# SENSOR_TESTER_EAGLE_SCHEMATIC.net
KiCad netlist of a schematic drawn in EAGLE
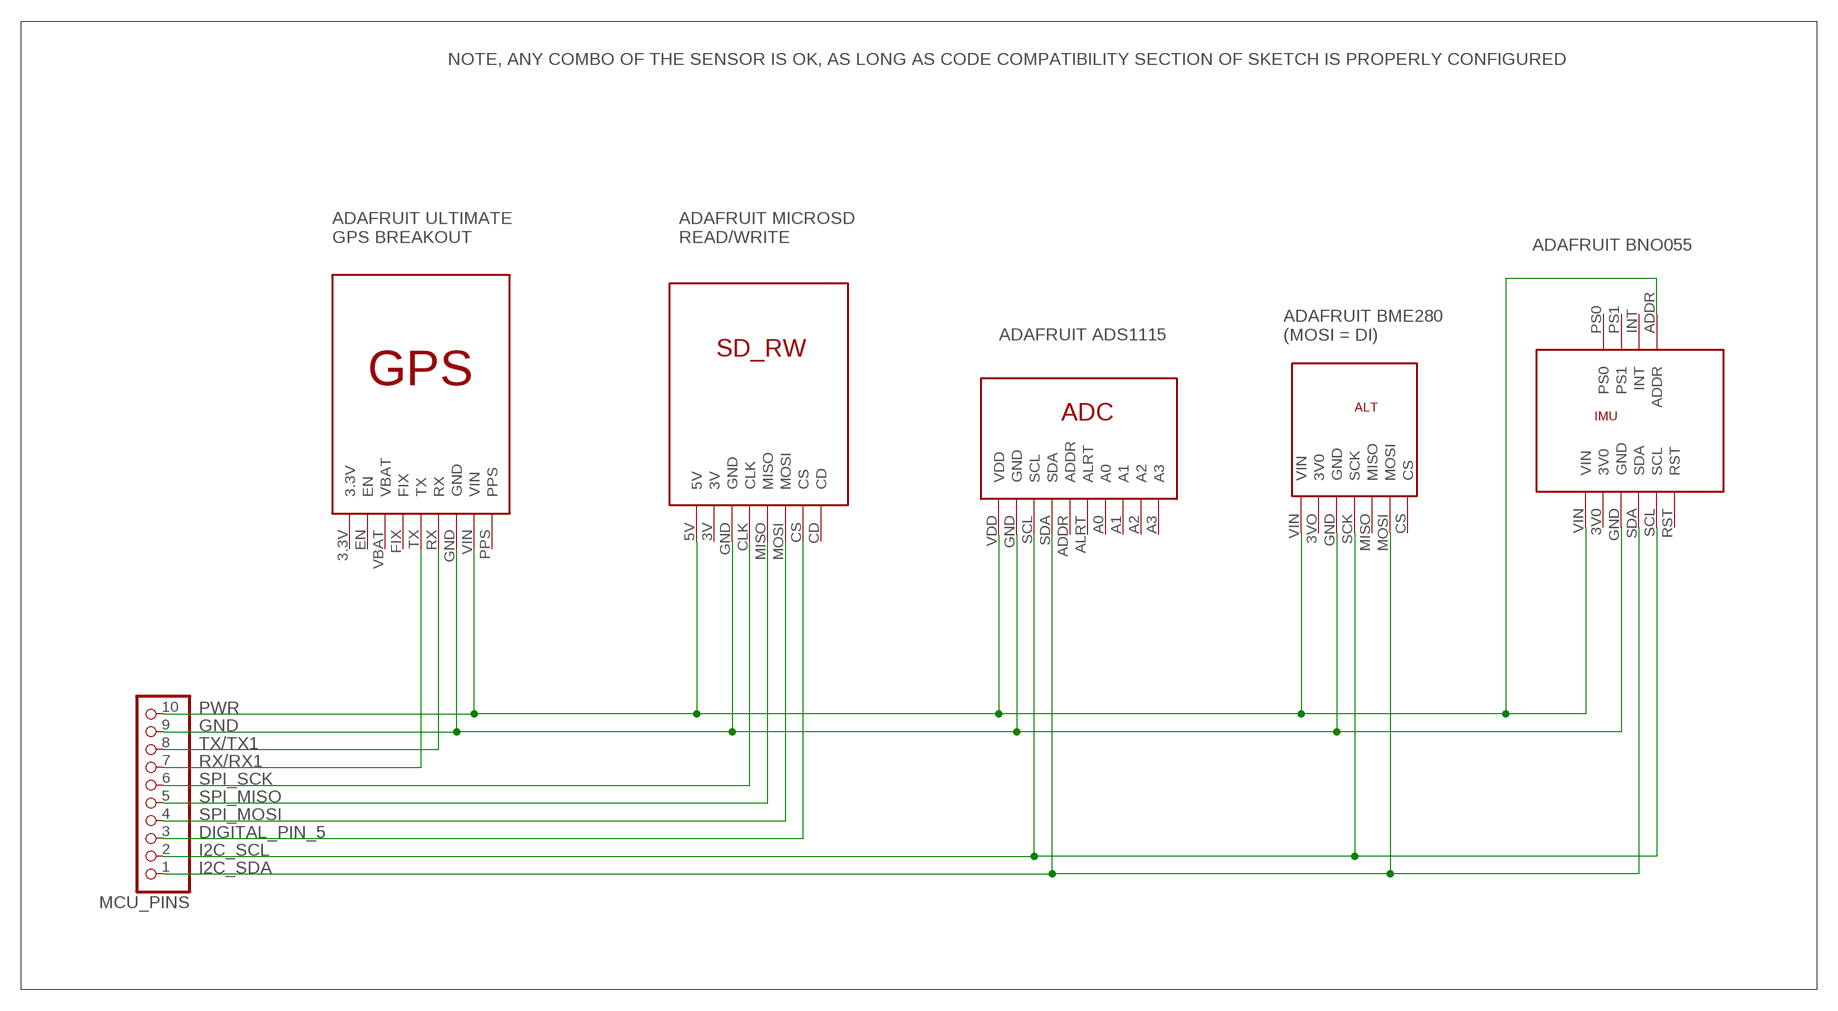
[diagram p0: schematic, sheet 1]

(export (version "E")
  (design (tool "Eeschema 10.0.6"))
  (components
    (comp (ref "MCU_PINS")
      (value "PINHD-1X10/90")
      (footprint "eagle-import:1X10_90")
      (libsource (lib "eagle-import") (part "PINHD-1X10/90"))
    )
    (comp (ref "U$1")
      (value "ADAFRUIT_GPS")
      (footprint "eagle-import:ADAFRUIT_GPS")
      (libsource (lib "eagle-import") (part "ADAFRUIT_GPS"))
    )
    (comp (ref "U$2")
      (value "ADAFRUI_SD_RW")
      (footprint "eagle-import:ADAFRUIT_SD_RW")
      (libsource (lib "eagle-import") (part "ADAFRUI_SD_RW"))
    )
    (comp (ref "U$3")
      (value "ADS1115")
      (footprint "eagle-import:ADS1115")
      (libsource (lib "eagle-import") (part "ADS1115"))
    )
    (comp (ref "U$4")
      (value "BME280")
      (footprint "eagle-import:BME280")
      (libsource (lib "eagle-import") (part "BME280"))
    )
    (comp (ref "U$5")
      (value "BNO055")
      (footprint "eagle-import:BNO055")
      (libsource (lib "eagle-import") (part "BNO055"))
    )
  )
  (nets
    (net (code "1") (name "/DIGITAL_PIN_5") (class "Default")
      (node (ref "MCU_PINS") (pin "3") (pinfunction "3_3") (pintype "passive"))
      (node (ref "U$2") (pin "CS") (pinfunction "CS_CS") (pintype "bidirectional"))
    )
    (net (code "2") (name "/GND") (class "Default")
      (node (ref "MCU_PINS") (pin "9") (pinfunction "9_9") (pintype "passive"))
      (node (ref "U$1") (pin "GND") (pinfunction "GND_GND") (pintype "bidirectional"))
      (node (ref "U$2") (pin "GND") (pinfunction "GND_GND") (pintype "bidirectional"))
      (node (ref "U$3") (pin "GND") (pinfunction "GND_GND") (pintype "bidirectional"))
      (node (ref "U$4") (pin "GND") (pinfunction "GND_GND") (pintype "bidirectional"))
      (node (ref "U$5") (pin "GND") (pinfunction "GND_GND") (pintype "bidirectional"))
    )
    (net (code "3") (name "/I2C_SCL") (class "Default")
      (node (ref "MCU_PINS") (pin "2") (pinfunction "2_2") (pintype "passive"))
      (node (ref "U$3") (pin "SCL") (pinfunction "SCL_SCL") (pintype "bidirectional"))
      (node (ref "U$4") (pin "SCK") (pinfunction "SCK_SCK") (pintype "bidirectional"))
      (node (ref "U$5") (pin "SCL") (pinfunction "SCL_SCL") (pintype "bidirectional"))
    )
    (net (code "4") (name "/I2C_SDA") (class "Default")
      (node (ref "MCU_PINS") (pin "1") (pinfunction "1_1") (pintype "passive"))
      (node (ref "U$3") (pin "SDA") (pinfunction "SDA_SDA") (pintype "bidirectional"))
      (node (ref "U$4") (pin "MOSI") (pinfunction "MOSI_MOSI") (pintype "bidirectional"))
      (node (ref "U$5") (pin "SDA") (pinfunction "SDA_SDA") (pintype "bidirectional"))
    )
    (net (code "5") (name "/PWR") (class "Default")
      (node (ref "MCU_PINS") (pin "10") (pinfunction "10_10") (pintype "passive"))
      (node (ref "U$1") (pin "VIN") (pinfunction "VIN_VIN") (pintype "bidirectional"))
      (node (ref "U$2") (pin "5V") (pinfunction "5V_5V") (pintype "bidirectional"))
      (node (ref "U$3") (pin "VDD") (pinfunction "VDD_VDD") (pintype "bidirectional"))
      (node (ref "U$4") (pin "VIN") (pinfunction "VIN_VIN") (pintype "bidirectional"))
      (node (ref "U$5") (pin "ADDR") (pinfunction "ADDR_ADDR") (pintype "bidirectional"))
      (node (ref "U$5") (pin "VIN") (pinfunction "VIN_VIN") (pintype "bidirectional"))
    )
    (net (code "6") (name "/RX{slash}RX1") (class "Default")
      (node (ref "MCU_PINS") (pin "7") (pinfunction "7_7") (pintype "passive"))
      (node (ref "U$1") (pin "TX") (pinfunction "TX_TX") (pintype "bidirectional"))
    )
    (net (code "7") (name "/SPI_MISO") (class "Default")
      (node (ref "MCU_PINS") (pin "5") (pinfunction "5_5") (pintype "passive"))
      (node (ref "U$2") (pin "MISO") (pinfunction "MISO_MISO") (pintype "bidirectional"))
    )
    (net (code "8") (name "/SPI_MOSI") (class "Default")
      (node (ref "MCU_PINS") (pin "4") (pinfunction "4_4") (pintype "passive"))
      (node (ref "U$2") (pin "MOSI") (pinfunction "MOSI_MOSI") (pintype "bidirectional"))
    )
    (net (code "9") (name "/SPI_SCK") (class "Default")
      (node (ref "MCU_PINS") (pin "6") (pinfunction "6_6") (pintype "passive"))
      (node (ref "U$2") (pin "CLK") (pinfunction "CLK_CLK") (pintype "bidirectional"))
    )
    (net (code "10") (name "/TX{slash}TX1") (class "Default")
      (node (ref "MCU_PINS") (pin "8") (pinfunction "8_8") (pintype "passive"))
      (node (ref "U$1") (pin "RX") (pinfunction "RX_RX") (pintype "bidirectional"))
    )
    (net (code "11") (name "unconnected-(U$1-Pad3.3V)") (class "Default")
      (node (ref "U$1") (pin "3.3V") (pinfunction "3.3V_3.3V") (pintype "bidirectional"))
    )
    (net (code "12") (name "unconnected-(U$1-PadEN)") (class "Default")
      (node (ref "U$1") (pin "EN") (pinfunction "EN_EN") (pintype "bidirectional"))
    )
    (net (code "13") (name "unconnected-(U$1-PadFIX)") (class "Default")
      (node (ref "U$1") (pin "FIX") (pinfunction "FIX_FIX") (pintype "bidirectional"))
    )
    (net (code "14") (name "unconnected-(U$1-PadPPS)") (class "Default")
      (node (ref "U$1") (pin "PPS") (pinfunction "PPS_PPS") (pintype "bidirectional"))
    )
    (net (code "15") (name "unconnected-(U$1-PadVBAT)") (class "Default")
      (node (ref "U$1") (pin "VBAT") (pinfunction "VBAT_VBAT") (pintype "bidirectional"))
    )
    (net (code "16") (name "unconnected-(U$2-Pad3V)") (class "Default")
      (node (ref "U$2") (pin "3V") (pinfunction "3V_3V") (pintype "bidirectional"))
    )
    (net (code "17") (name "unconnected-(U$2-PadCD)") (class "Default")
      (node (ref "U$2") (pin "CD") (pinfunction "CD_CD") (pintype "bidirectional"))
    )
    (net (code "18") (name "unconnected-(U$3-PadA0)") (class "Default")
      (node (ref "U$3") (pin "A0") (pinfunction "A0_A0") (pintype "bidirectional"))
    )
    (net (code "19") (name "unconnected-(U$3-PadA1)") (class "Default")
      (node (ref "U$3") (pin "A1") (pinfunction "A1_A1") (pintype "bidirectional"))
    )
    (net (code "20") (name "unconnected-(U$3-PadA2)") (class "Default")
      (node (ref "U$3") (pin "A2") (pinfunction "A2_A2") (pintype "bidirectional"))
    )
    (net (code "21") (name "unconnected-(U$3-PadA3)") (class "Default")
      (node (ref "U$3") (pin "A3") (pinfunction "A3_A3") (pintype "bidirectional"))
    )
    (net (code "22") (name "unconnected-(U$3-PadADDR)") (class "Default")
      (node (ref "U$3") (pin "ADDR") (pinfunction "ADDR_ADDR") (pintype "bidirectional"))
    )
    (net (code "23") (name "unconnected-(U$3-PadALRT)") (class "Default")
      (node (ref "U$3") (pin "ALRT") (pinfunction "ALRT_ALRT") (pintype "bidirectional"))
    )
    (net (code "24") (name "unconnected-(U$4-3V0-Pad3VO)") (class "Default")
      (node (ref "U$4") (pin "3VO") (pinfunction "3V0_3VO") (pintype "bidirectional"))
    )
    (net (code "25") (name "unconnected-(U$4-PadCS)") (class "Default")
      (node (ref "U$4") (pin "CS") (pinfunction "CS_CS") (pintype "bidirectional"))
    )
    (net (code "26") (name "unconnected-(U$4-PadMISO)") (class "Default")
      (node (ref "U$4") (pin "MISO") (pinfunction "MISO_MISO") (pintype "bidirectional"))
    )
    (net (code "27") (name "unconnected-(U$5-Pad3V0)") (class "Default")
      (node (ref "U$5") (pin "3V0") (pinfunction "3V0_3V0") (pintype "bidirectional"))
    )
    (net (code "28") (name "unconnected-(U$5-PadINT)") (class "Default")
      (node (ref "U$5") (pin "INT") (pinfunction "INT_INT") (pintype "bidirectional"))
    )
    (net (code "29") (name "unconnected-(U$5-PadPS0)") (class "Default")
      (node (ref "U$5") (pin "PS0") (pinfunction "PS0_PS0") (pintype "bidirectional"))
    )
    (net (code "30") (name "unconnected-(U$5-PadPS1)") (class "Default")
      (node (ref "U$5") (pin "PS1") (pinfunction "PS1_PS1") (pintype "bidirectional"))
    )
    (net (code "31") (name "unconnected-(U$5-PadRST)") (class "Default")
      (node (ref "U$5") (pin "RST") (pinfunction "RST_RST") (pintype "bidirectional"))
    )
  )
)
